# hirose_omnetics_adapter_schematic.net
KiCad netlist of a schematic drawn in EAGLE
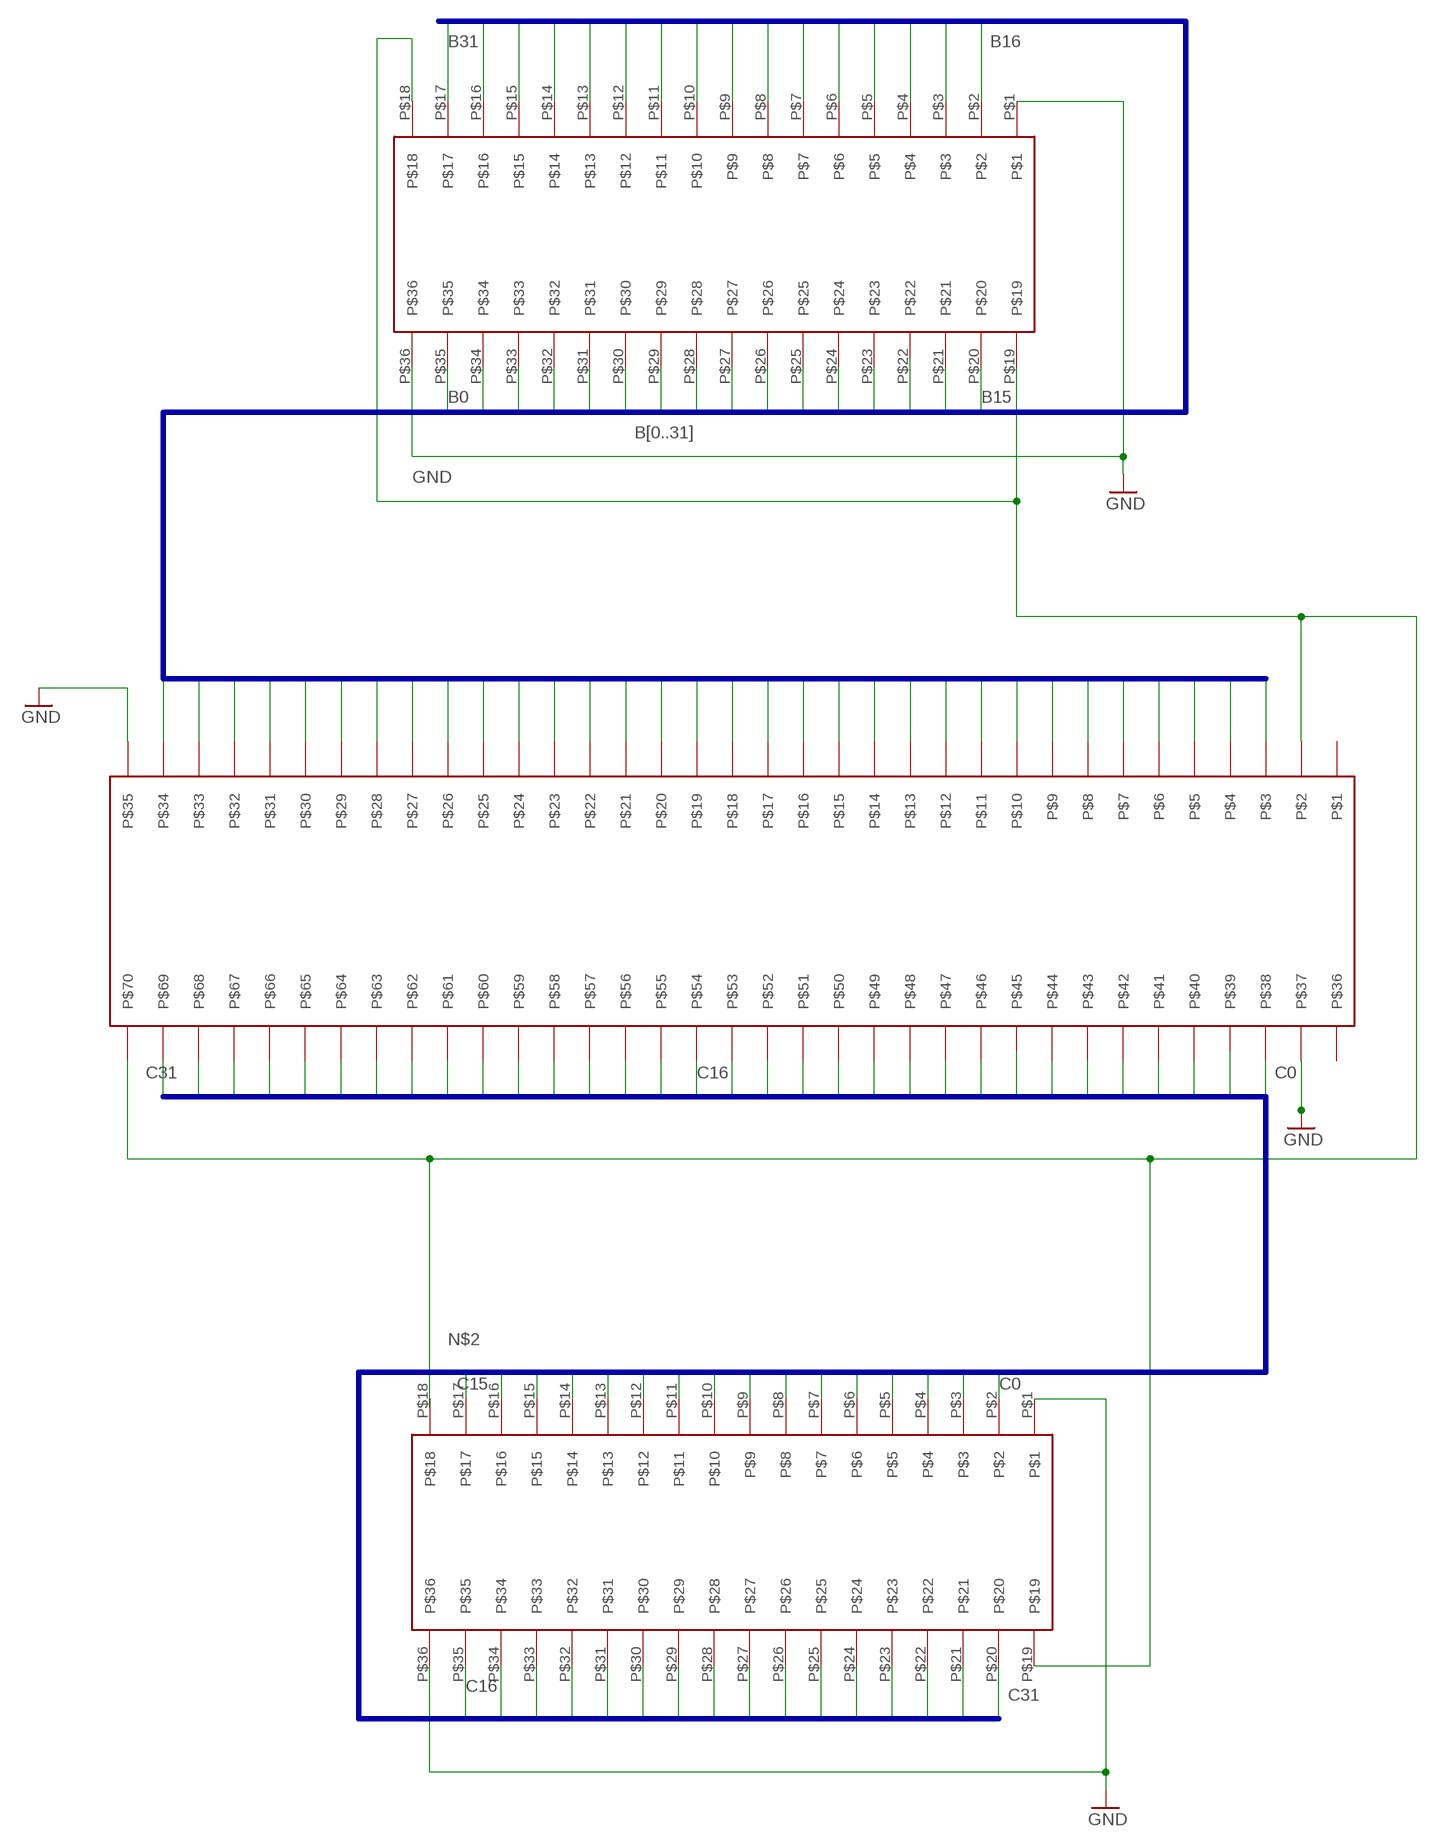
[diagram p0: schematic, sheet 1]

(export (version "E")
  (design (tool "Eeschema 10.0.6"))
  (components
    (comp (ref "U$1")
      (value "HIROSE_DF40_70PIN")
      (footprint "eagle-import:HIROSE_DF40C-70DS")
      (libsource (lib "eagle-import") (part "HIROSE_DF40_70PIN"))
    )
    (comp (ref "U$2")
      (value "OMNETICS_A79026")
      (footprint "eagle-import:OMNETICS_A79026-001")
      (libsource (lib "eagle-import") (part "OMNETICS_A79026"))
    )
    (comp (ref "U$3")
      (value "OMNETICS_A79026")
      (footprint "eagle-import:OMNETICS_A79026-001")
      (libsource (lib "eagle-import") (part "OMNETICS_A79026"))
    )
  )
  (nets
    (net (code "1") (name "/B0") (class "Default")
      (node (ref "U$1") (pin "P$3") (pinfunction "P$3_P$3") (pintype "bidirectional"))
      (node (ref "U$2") (pin "P$35") (pinfunction "P$35_P$35") (pintype "bidirectional"))
    )
    (net (code "2") (name "/B1") (class "Default")
      (node (ref "U$1") (pin "P$4") (pinfunction "P$4_P$4") (pintype "bidirectional"))
      (node (ref "U$2") (pin "P$34") (pinfunction "P$34_P$34") (pintype "bidirectional"))
    )
    (net (code "3") (name "/B2") (class "Default")
      (node (ref "U$1") (pin "P$5") (pinfunction "P$5_P$5") (pintype "bidirectional"))
      (node (ref "U$2") (pin "P$33") (pinfunction "P$33_P$33") (pintype "bidirectional"))
    )
    (net (code "4") (name "/B3") (class "Default")
      (node (ref "U$1") (pin "P$6") (pinfunction "P$6_P$6") (pintype "bidirectional"))
      (node (ref "U$2") (pin "P$32") (pinfunction "P$32_P$32") (pintype "bidirectional"))
    )
    (net (code "5") (name "/B4") (class "Default")
      (node (ref "U$1") (pin "P$7") (pinfunction "P$7_P$7") (pintype "bidirectional"))
      (node (ref "U$2") (pin "P$31") (pinfunction "P$31_P$31") (pintype "bidirectional"))
    )
    (net (code "6") (name "/B5") (class "Default")
      (node (ref "U$1") (pin "P$8") (pinfunction "P$8_P$8") (pintype "bidirectional"))
      (node (ref "U$2") (pin "P$30") (pinfunction "P$30_P$30") (pintype "bidirectional"))
    )
    (net (code "7") (name "/B6") (class "Default")
      (node (ref "U$1") (pin "P$9") (pinfunction "P$9_P$9") (pintype "bidirectional"))
      (node (ref "U$2") (pin "P$29") (pinfunction "P$29_P$29") (pintype "bidirectional"))
    )
    (net (code "8") (name "/B7") (class "Default")
      (node (ref "U$1") (pin "P$10") (pinfunction "P$10_P$10") (pintype "bidirectional"))
      (node (ref "U$2") (pin "P$28") (pinfunction "P$28_P$28") (pintype "bidirectional"))
    )
    (net (code "9") (name "/B8") (class "Default")
      (node (ref "U$1") (pin "P$11") (pinfunction "P$11_P$11") (pintype "bidirectional"))
      (node (ref "U$2") (pin "P$27") (pinfunction "P$27_P$27") (pintype "bidirectional"))
    )
    (net (code "10") (name "/B9") (class "Default")
      (node (ref "U$1") (pin "P$12") (pinfunction "P$12_P$12") (pintype "bidirectional"))
      (node (ref "U$2") (pin "P$26") (pinfunction "P$26_P$26") (pintype "bidirectional"))
    )
    (net (code "11") (name "/B10") (class "Default")
      (node (ref "U$1") (pin "P$13") (pinfunction "P$13_P$13") (pintype "bidirectional"))
      (node (ref "U$2") (pin "P$25") (pinfunction "P$25_P$25") (pintype "bidirectional"))
    )
    (net (code "12") (name "/B11") (class "Default")
      (node (ref "U$1") (pin "P$14") (pinfunction "P$14_P$14") (pintype "bidirectional"))
      (node (ref "U$2") (pin "P$24") (pinfunction "P$24_P$24") (pintype "bidirectional"))
    )
    (net (code "13") (name "/B12") (class "Default")
      (node (ref "U$1") (pin "P$15") (pinfunction "P$15_P$15") (pintype "bidirectional"))
      (node (ref "U$2") (pin "P$23") (pinfunction "P$23_P$23") (pintype "bidirectional"))
    )
    (net (code "14") (name "/B13") (class "Default")
      (node (ref "U$1") (pin "P$16") (pinfunction "P$16_P$16") (pintype "bidirectional"))
    )
    (net (code "15") (name "/B14") (class "Default")
      (node (ref "U$1") (pin "P$17") (pinfunction "P$17_P$17") (pintype "bidirectional"))
      (node (ref "U$2") (pin "P$21") (pinfunction "P$21_P$21") (pintype "bidirectional"))
    )
    (net (code "16") (name "/B15") (class "Default")
      (node (ref "U$1") (pin "P$18") (pinfunction "P$18_P$18") (pintype "bidirectional"))
      (node (ref "U$2") (pin "P$20") (pinfunction "P$20_P$20") (pintype "bidirectional"))
    )
    (net (code "17") (name "/B16") (class "Default")
      (node (ref "U$1") (pin "P$19") (pinfunction "P$19_P$19") (pintype "bidirectional"))
      (node (ref "U$2") (pin "P$2") (pinfunction "P$2_P$2") (pintype "bidirectional"))
    )
    (net (code "18") (name "/B17") (class "Default")
      (node (ref "U$1") (pin "P$20") (pinfunction "P$20_P$20") (pintype "bidirectional"))
      (node (ref "U$2") (pin "P$3") (pinfunction "P$3_P$3") (pintype "bidirectional"))
    )
    (net (code "19") (name "/B18") (class "Default")
      (node (ref "U$1") (pin "P$21") (pinfunction "P$21_P$21") (pintype "bidirectional"))
      (node (ref "U$2") (pin "P$4") (pinfunction "P$4_P$4") (pintype "bidirectional"))
    )
    (net (code "20") (name "/B19") (class "Default")
      (node (ref "U$1") (pin "P$22") (pinfunction "P$22_P$22") (pintype "bidirectional"))
      (node (ref "U$2") (pin "P$5") (pinfunction "P$5_P$5") (pintype "bidirectional"))
    )
    (net (code "21") (name "/B20") (class "Default")
      (node (ref "U$1") (pin "P$23") (pinfunction "P$23_P$23") (pintype "bidirectional"))
      (node (ref "U$2") (pin "P$6") (pinfunction "P$6_P$6") (pintype "bidirectional"))
    )
    (net (code "22") (name "/B21") (class "Default")
      (node (ref "U$1") (pin "P$24") (pinfunction "P$24_P$24") (pintype "bidirectional"))
      (node (ref "U$2") (pin "P$7") (pinfunction "P$7_P$7") (pintype "bidirectional"))
    )
    (net (code "23") (name "/B22") (class "Default")
      (node (ref "U$1") (pin "P$25") (pinfunction "P$25_P$25") (pintype "bidirectional"))
      (node (ref "U$2") (pin "P$8") (pinfunction "P$8_P$8") (pintype "bidirectional"))
    )
    (net (code "24") (name "/B23") (class "Default")
      (node (ref "U$1") (pin "P$26") (pinfunction "P$26_P$26") (pintype "bidirectional"))
      (node (ref "U$2") (pin "P$9") (pinfunction "P$9_P$9") (pintype "bidirectional"))
    )
    (net (code "25") (name "/B24") (class "Default")
      (node (ref "U$1") (pin "P$27") (pinfunction "P$27_P$27") (pintype "bidirectional"))
      (node (ref "U$2") (pin "P$10") (pinfunction "P$10_P$10") (pintype "bidirectional"))
    )
    (net (code "26") (name "/B25") (class "Default")
      (node (ref "U$1") (pin "P$28") (pinfunction "P$28_P$28") (pintype "bidirectional"))
      (node (ref "U$2") (pin "P$11") (pinfunction "P$11_P$11") (pintype "bidirectional"))
    )
    (net (code "27") (name "/B26") (class "Default")
      (node (ref "U$1") (pin "P$29") (pinfunction "P$29_P$29") (pintype "bidirectional"))
      (node (ref "U$2") (pin "P$12") (pinfunction "P$12_P$12") (pintype "bidirectional"))
    )
    (net (code "28") (name "/B27") (class "Default")
      (node (ref "U$1") (pin "P$30") (pinfunction "P$30_P$30") (pintype "bidirectional"))
      (node (ref "U$2") (pin "P$13") (pinfunction "P$13_P$13") (pintype "bidirectional"))
    )
    (net (code "29") (name "/B28") (class "Default")
      (node (ref "U$1") (pin "P$31") (pinfunction "P$31_P$31") (pintype "bidirectional"))
      (node (ref "U$2") (pin "P$14") (pinfunction "P$14_P$14") (pintype "bidirectional"))
    )
    (net (code "30") (name "/B29") (class "Default")
      (node (ref "U$1") (pin "P$32") (pinfunction "P$32_P$32") (pintype "bidirectional"))
      (node (ref "U$2") (pin "P$15") (pinfunction "P$15_P$15") (pintype "bidirectional"))
    )
    (net (code "31") (name "/B30") (class "Default")
      (node (ref "U$1") (pin "P$33") (pinfunction "P$33_P$33") (pintype "bidirectional"))
      (node (ref "U$2") (pin "P$16") (pinfunction "P$16_P$16") (pintype "bidirectional"))
    )
    (net (code "32") (name "/B31") (class "Default")
      (node (ref "U$1") (pin "P$34") (pinfunction "P$34_P$34") (pintype "bidirectional"))
      (node (ref "U$2") (pin "P$17") (pinfunction "P$17_P$17") (pintype "bidirectional"))
    )
    (net (code "34") (name "/C0") (class "Default")
      (node (ref "U$1") (pin "P$38") (pinfunction "P$38_P$38") (pintype "bidirectional"))
      (node (ref "U$3") (pin "P$2") (pinfunction "P$2_P$2") (pintype "bidirectional"))
    )
    (net (code "35") (name "/C1") (class "Default")
      (node (ref "U$3") (pin "P$3") (pinfunction "P$3_P$3") (pintype "bidirectional"))
    )
    (net (code "36") (name "/C2") (class "Default")
      (node (ref "U$1") (pin "P$40") (pinfunction "P$40_P$40") (pintype "bidirectional"))
      (node (ref "U$3") (pin "P$4") (pinfunction "P$4_P$4") (pintype "bidirectional"))
    )
    (net (code "37") (name "/C3") (class "Default")
      (node (ref "U$1") (pin "P$41") (pinfunction "P$41_P$41") (pintype "bidirectional"))
      (node (ref "U$3") (pin "P$5") (pinfunction "P$5_P$5") (pintype "bidirectional"))
    )
    (net (code "38") (name "/C4") (class "Default")
      (node (ref "U$1") (pin "P$42") (pinfunction "P$42_P$42") (pintype "bidirectional"))
      (node (ref "U$3") (pin "P$6") (pinfunction "P$6_P$6") (pintype "bidirectional"))
    )
    (net (code "39") (name "/C5") (class "Default")
      (node (ref "U$1") (pin "P$43") (pinfunction "P$43_P$43") (pintype "bidirectional"))
      (node (ref "U$3") (pin "P$7") (pinfunction "P$7_P$7") (pintype "bidirectional"))
    )
    (net (code "40") (name "/C6") (class "Default")
      (node (ref "U$1") (pin "P$44") (pinfunction "P$44_P$44") (pintype "bidirectional"))
      (node (ref "U$3") (pin "P$8") (pinfunction "P$8_P$8") (pintype "bidirectional"))
    )
    (net (code "41") (name "/C7") (class "Default")
      (node (ref "U$3") (pin "P$9") (pinfunction "P$9_P$9") (pintype "bidirectional"))
    )
    (net (code "42") (name "/C8") (class "Default")
      (node (ref "U$1") (pin "P$46") (pinfunction "P$46_P$46") (pintype "bidirectional"))
      (node (ref "U$3") (pin "P$10") (pinfunction "P$10_P$10") (pintype "bidirectional"))
    )
    (net (code "43") (name "/C9") (class "Default")
      (node (ref "U$1") (pin "P$47") (pinfunction "P$47_P$47") (pintype "bidirectional"))
      (node (ref "U$3") (pin "P$11") (pinfunction "P$11_P$11") (pintype "bidirectional"))
    )
    (net (code "44") (name "/C10") (class "Default")
      (node (ref "U$1") (pin "P$48") (pinfunction "P$48_P$48") (pintype "bidirectional"))
      (node (ref "U$3") (pin "P$12") (pinfunction "P$12_P$12") (pintype "bidirectional"))
    )
    (net (code "45") (name "/C11") (class "Default")
      (node (ref "U$1") (pin "P$49") (pinfunction "P$49_P$49") (pintype "bidirectional"))
      (node (ref "U$3") (pin "P$13") (pinfunction "P$13_P$13") (pintype "bidirectional"))
    )
    (net (code "46") (name "/C12") (class "Default")
      (node (ref "U$1") (pin "P$50") (pinfunction "P$50_P$50") (pintype "bidirectional"))
      (node (ref "U$3") (pin "P$14") (pinfunction "P$14_P$14") (pintype "bidirectional"))
    )
    (net (code "47") (name "/C13") (class "Default")
      (node (ref "U$1") (pin "P$51") (pinfunction "P$51_P$51") (pintype "bidirectional"))
      (node (ref "U$3") (pin "P$15") (pinfunction "P$15_P$15") (pintype "bidirectional"))
    )
    (net (code "48") (name "/C14") (class "Default")
      (node (ref "U$1") (pin "P$52") (pinfunction "P$52_P$52") (pintype "bidirectional"))
      (node (ref "U$3") (pin "P$16") (pinfunction "P$16_P$16") (pintype "bidirectional"))
    )
    (net (code "49") (name "/C15") (class "Default")
      (node (ref "U$1") (pin "P$53") (pinfunction "P$53_P$53") (pintype "bidirectional"))
      (node (ref "U$3") (pin "P$17") (pinfunction "P$17_P$17") (pintype "bidirectional"))
    )
    (net (code "50") (name "/C16") (class "Default")
      (node (ref "U$1") (pin "P$54") (pinfunction "P$54_P$54") (pintype "bidirectional"))
      (node (ref "U$3") (pin "P$35") (pinfunction "P$35_P$35") (pintype "bidirectional"))
    )
    (net (code "51") (name "/C17") (class "Default")
      (node (ref "U$1") (pin "P$55") (pinfunction "P$55_P$55") (pintype "bidirectional"))
      (node (ref "U$3") (pin "P$34") (pinfunction "P$34_P$34") (pintype "bidirectional"))
    )
    (net (code "52") (name "/C18") (class "Default")
      (node (ref "U$1") (pin "P$56") (pinfunction "P$56_P$56") (pintype "bidirectional"))
      (node (ref "U$3") (pin "P$33") (pinfunction "P$33_P$33") (pintype "bidirectional"))
    )
    (net (code "53") (name "/C19") (class "Default")
      (node (ref "U$1") (pin "P$57") (pinfunction "P$57_P$57") (pintype "bidirectional"))
      (node (ref "U$3") (pin "P$32") (pinfunction "P$32_P$32") (pintype "bidirectional"))
    )
    (net (code "54") (name "/C20") (class "Default")
      (node (ref "U$1") (pin "P$58") (pinfunction "P$58_P$58") (pintype "bidirectional"))
      (node (ref "U$3") (pin "P$31") (pinfunction "P$31_P$31") (pintype "bidirectional"))
    )
    (net (code "55") (name "/C21") (class "Default")
      (node (ref "U$1") (pin "P$59") (pinfunction "P$59_P$59") (pintype "bidirectional"))
      (node (ref "U$3") (pin "P$30") (pinfunction "P$30_P$30") (pintype "bidirectional"))
    )
    (net (code "56") (name "/C22") (class "Default")
      (node (ref "U$1") (pin "P$60") (pinfunction "P$60_P$60") (pintype "bidirectional"))
      (node (ref "U$3") (pin "P$29") (pinfunction "P$29_P$29") (pintype "bidirectional"))
    )
    (net (code "57") (name "/C23") (class "Default")
      (node (ref "U$1") (pin "P$61") (pinfunction "P$61_P$61") (pintype "bidirectional"))
      (node (ref "U$3") (pin "P$28") (pinfunction "P$28_P$28") (pintype "bidirectional"))
    )
    (net (code "58") (name "/C24") (class "Default")
      (node (ref "U$1") (pin "P$62") (pinfunction "P$62_P$62") (pintype "bidirectional"))
      (node (ref "U$3") (pin "P$27") (pinfunction "P$27_P$27") (pintype "bidirectional"))
    )
    (net (code "59") (name "/C25") (class "Default")
      (node (ref "U$1") (pin "P$63") (pinfunction "P$63_P$63") (pintype "bidirectional"))
      (node (ref "U$3") (pin "P$26") (pinfunction "P$26_P$26") (pintype "bidirectional"))
    )
    (net (code "60") (name "/C26") (class "Default")
      (node (ref "U$1") (pin "P$64") (pinfunction "P$64_P$64") (pintype "bidirectional"))
      (node (ref "U$3") (pin "P$25") (pinfunction "P$25_P$25") (pintype "bidirectional"))
    )
    (net (code "61") (name "/C27") (class "Default")
      (node (ref "U$1") (pin "P$65") (pinfunction "P$65_P$65") (pintype "bidirectional"))
      (node (ref "U$3") (pin "P$24") (pinfunction "P$24_P$24") (pintype "bidirectional"))
    )
    (net (code "62") (name "/C28") (class "Default")
      (node (ref "U$1") (pin "P$66") (pinfunction "P$66_P$66") (pintype "bidirectional"))
      (node (ref "U$3") (pin "P$23") (pinfunction "P$23_P$23") (pintype "bidirectional"))
    )
    (net (code "63") (name "/C29") (class "Default")
      (node (ref "U$1") (pin "P$67") (pinfunction "P$67_P$67") (pintype "bidirectional"))
      (node (ref "U$3") (pin "P$22") (pinfunction "P$22_P$22") (pintype "bidirectional"))
    )
    (net (code "64") (name "/C30") (class "Default")
      (node (ref "U$1") (pin "P$68") (pinfunction "P$68_P$68") (pintype "bidirectional"))
      (node (ref "U$3") (pin "P$21") (pinfunction "P$21_P$21") (pintype "bidirectional"))
    )
    (net (code "65") (name "/C31") (class "Default")
      (node (ref "U$1") (pin "P$69") (pinfunction "P$69_P$69") (pintype "bidirectional"))
      (node (ref "U$3") (pin "P$20") (pinfunction "P$20_P$20") (pintype "bidirectional"))
    )
    (net (code "66") (name "/N$2") (class "Default")
      (node (ref "U$1") (pin "P$2") (pinfunction "P$2_P$2") (pintype "bidirectional"))
      (node (ref "U$1") (pin "P$70") (pinfunction "P$70_P$70") (pintype "bidirectional"))
      (node (ref "U$2") (pin "P$18") (pinfunction "P$18_P$18") (pintype "bidirectional"))
      (node (ref "U$2") (pin "P$19") (pinfunction "P$19_P$19") (pintype "bidirectional"))
      (node (ref "U$3") (pin "P$19") (pinfunction "P$19_P$19") (pintype "bidirectional"))
    )
    (net (code "67") (name "GND") (class "Default")
      (node (ref "U$1") (pin "P$35") (pinfunction "P$35_P$35") (pintype "bidirectional"))
      (node (ref "U$1") (pin "P$37") (pinfunction "P$37_P$37") (pintype "bidirectional"))
      (node (ref "U$2") (pin "P$1") (pinfunction "P$1_P$1") (pintype "bidirectional"))
      (node (ref "U$2") (pin "P$36") (pinfunction "P$36_P$36") (pintype "bidirectional"))
      (node (ref "U$3") (pin "P$1") (pinfunction "P$1_P$1") (pintype "bidirectional"))
      (node (ref "U$3") (pin "P$36") (pinfunction "P$36_P$36") (pintype "bidirectional"))
    )
    (net (code "68") (name "unconnected-(U$1-PadP$1)") (class "Default")
      (node (ref "U$1") (pin "P$1") (pinfunction "P$1_P$1") (pintype "bidirectional"))
    )
    (net (code "69") (name "unconnected-(U$1-PadP$36)") (class "Default")
      (node (ref "U$1") (pin "P$36") (pinfunction "P$36_P$36") (pintype "bidirectional"))
    )
    (net (code "70") (name "unconnected-(U$1-PadP$39)") (class "Default")
      (node (ref "U$1") (pin "P$39") (pinfunction "P$39_P$39") (pintype "bidirectional"))
    )
    (net (code "71") (name "unconnected-(U$1-PadP$45)") (class "Default")
      (node (ref "U$1") (pin "P$45") (pinfunction "P$45_P$45") (pintype "bidirectional"))
    )
    (net (code "72") (name "unconnected-(U$2-PadP$22)") (class "Default")
      (node (ref "U$2") (pin "P$22") (pinfunction "P$22_P$22") (pintype "bidirectional"))
    )
    (net (code "73") (name "unconnected-(U$3-PadP$18)") (class "Default")
      (node (ref "U$3") (pin "P$18") (pinfunction "P$18_P$18") (pintype "bidirectional"))
    )
  )
)
